# PaxGeo_SolenoidBoard.net
KiCad netlist of a schematic drawn in EAGLE
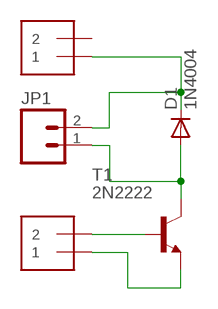
[diagram p0: schematic, sheet 1]

(export (version "E")
  (design (tool "Eeschema 10.0.6"))
  (components
    (comp (ref "D1")
      (value "1N4004")
      (footprint "eagle-import:DO41-10")
      (libsource (lib "eagle-import") (part "1N4004"))
    )
    (comp (ref "J1")
      (value "1X2-3.5MM")
      (footprint "eagle-import:1X2-3.5MM")
      (libsource (lib "eagle-import") (part "1X2-3.5MM"))
    )
    (comp (ref "J2")
      (value "1X2-3.5MM")
      (footprint "eagle-import:1X2-3.5MM")
      (libsource (lib "eagle-import") (part "1X2-3.5MM"))
    )
    (comp (ref "JP1")
      (value "M02LOCK_LONGPADS")
      (footprint "eagle-import:1X02_LOCK_LONGPADS")
      (libsource (lib "eagle-import") (part "M02LOCK_LONGPADS"))
    )
    (comp (ref "T1")
      (value "2N2222")
      (footprint "eagle-import:TO92-EBC-OVAL")
      (libsource (lib "eagle-import") (part "2N2222"))
    )
  )
  (nets
    (net (code "1") (name "Net-(D1-PadA)") (class "Default")
      (node (ref "D1") (pin "A") (pinfunction "A_A") (pintype "passive"))
      (node (ref "JP1") (pin "1") (pinfunction "1_1") (pintype "passive"))
      (node (ref "T1") (pin "C") (pinfunction "C_C") (pintype "passive"))
    )
    (net (code "2") (name "Net-(D1-PadC)") (class "Default")
      (node (ref "D1") (pin "C") (pinfunction "C_C") (pintype "passive"))
      (node (ref "J2") (pin "1") (pinfunction "1_1") (pintype "passive"))
      (node (ref "JP1") (pin "2") (pinfunction "2_2") (pintype "passive"))
    )
    (net (code "3") (name "Net-(J1-Pad1)") (class "Default")
      (node (ref "J1") (pin "1") (pinfunction "1_1") (pintype "passive"))
      (node (ref "T1") (pin "E") (pinfunction "E_E") (pintype "passive"))
    )
    (net (code "4") (name "Net-(J1-Pad2)") (class "Default")
      (node (ref "J1") (pin "2") (pinfunction "2_2") (pintype "passive"))
      (node (ref "T1") (pin "B") (pinfunction "B_B") (pintype "passive"))
    )
    (net (code "5") (name "unconnected-(J2-Pad2)") (class "Default")
      (node (ref "J2") (pin "2") (pinfunction "2_2") (pintype "passive"))
    )
  )
)
